# C0603C101J5HACAUTO.net
KiCad netlist of a schematic drawn in Altium Designer
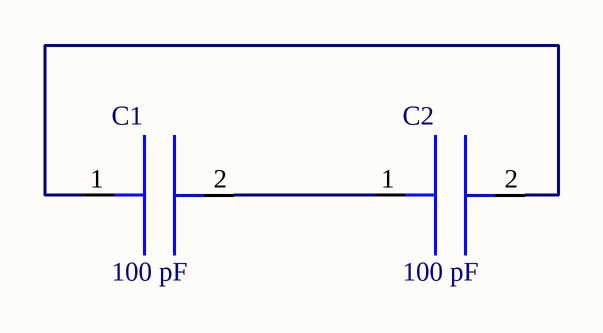
[diagram p0: C0603C101J5HACAUTO.SchDoc]

(export (version "E")
  (design (tool "Eeschema 10.0.6"))
  (components
    (comp (ref "C1")
      (value "100 pF")
      (footprint "C0603C101J5HACAUTO")
      (description "Capacitor Cerámico SMD 0603, 50V, +/-5%, C0G")
      (libsource (lib "C0603C101J5HACAUTO") (part "C0603C101J5HACAUTO"))
    )
    (comp (ref "C2")
      (value "100 pF")
      (footprint "C0603C101J5HACAUTO")
      (description "Capacitor Cerámico SMD 0603, 50V, +/-5%, C0G")
      (libsource (lib "C0603C101J5HACAUTO") (part "C0603C101J5HACAUTO"))
    )
  )
  (nets
    (net (code "1") (name "Net-(C1-Pad1)") (class "Default")
      (node (ref "C1") (pin "1") (pintype "passive"))
      (node (ref "C2") (pin "2") (pintype "passive"))
    )
    (net (code "2") (name "Net-(C1-Pad2)") (class "Default")
      (node (ref "C1") (pin "2") (pintype "passive"))
      (node (ref "C2") (pin "1") (pintype "passive"))
    )
  )
)
